# ISL6236A_DEMO.net
KiCad netlist of a schematic drawn in Altium Designer
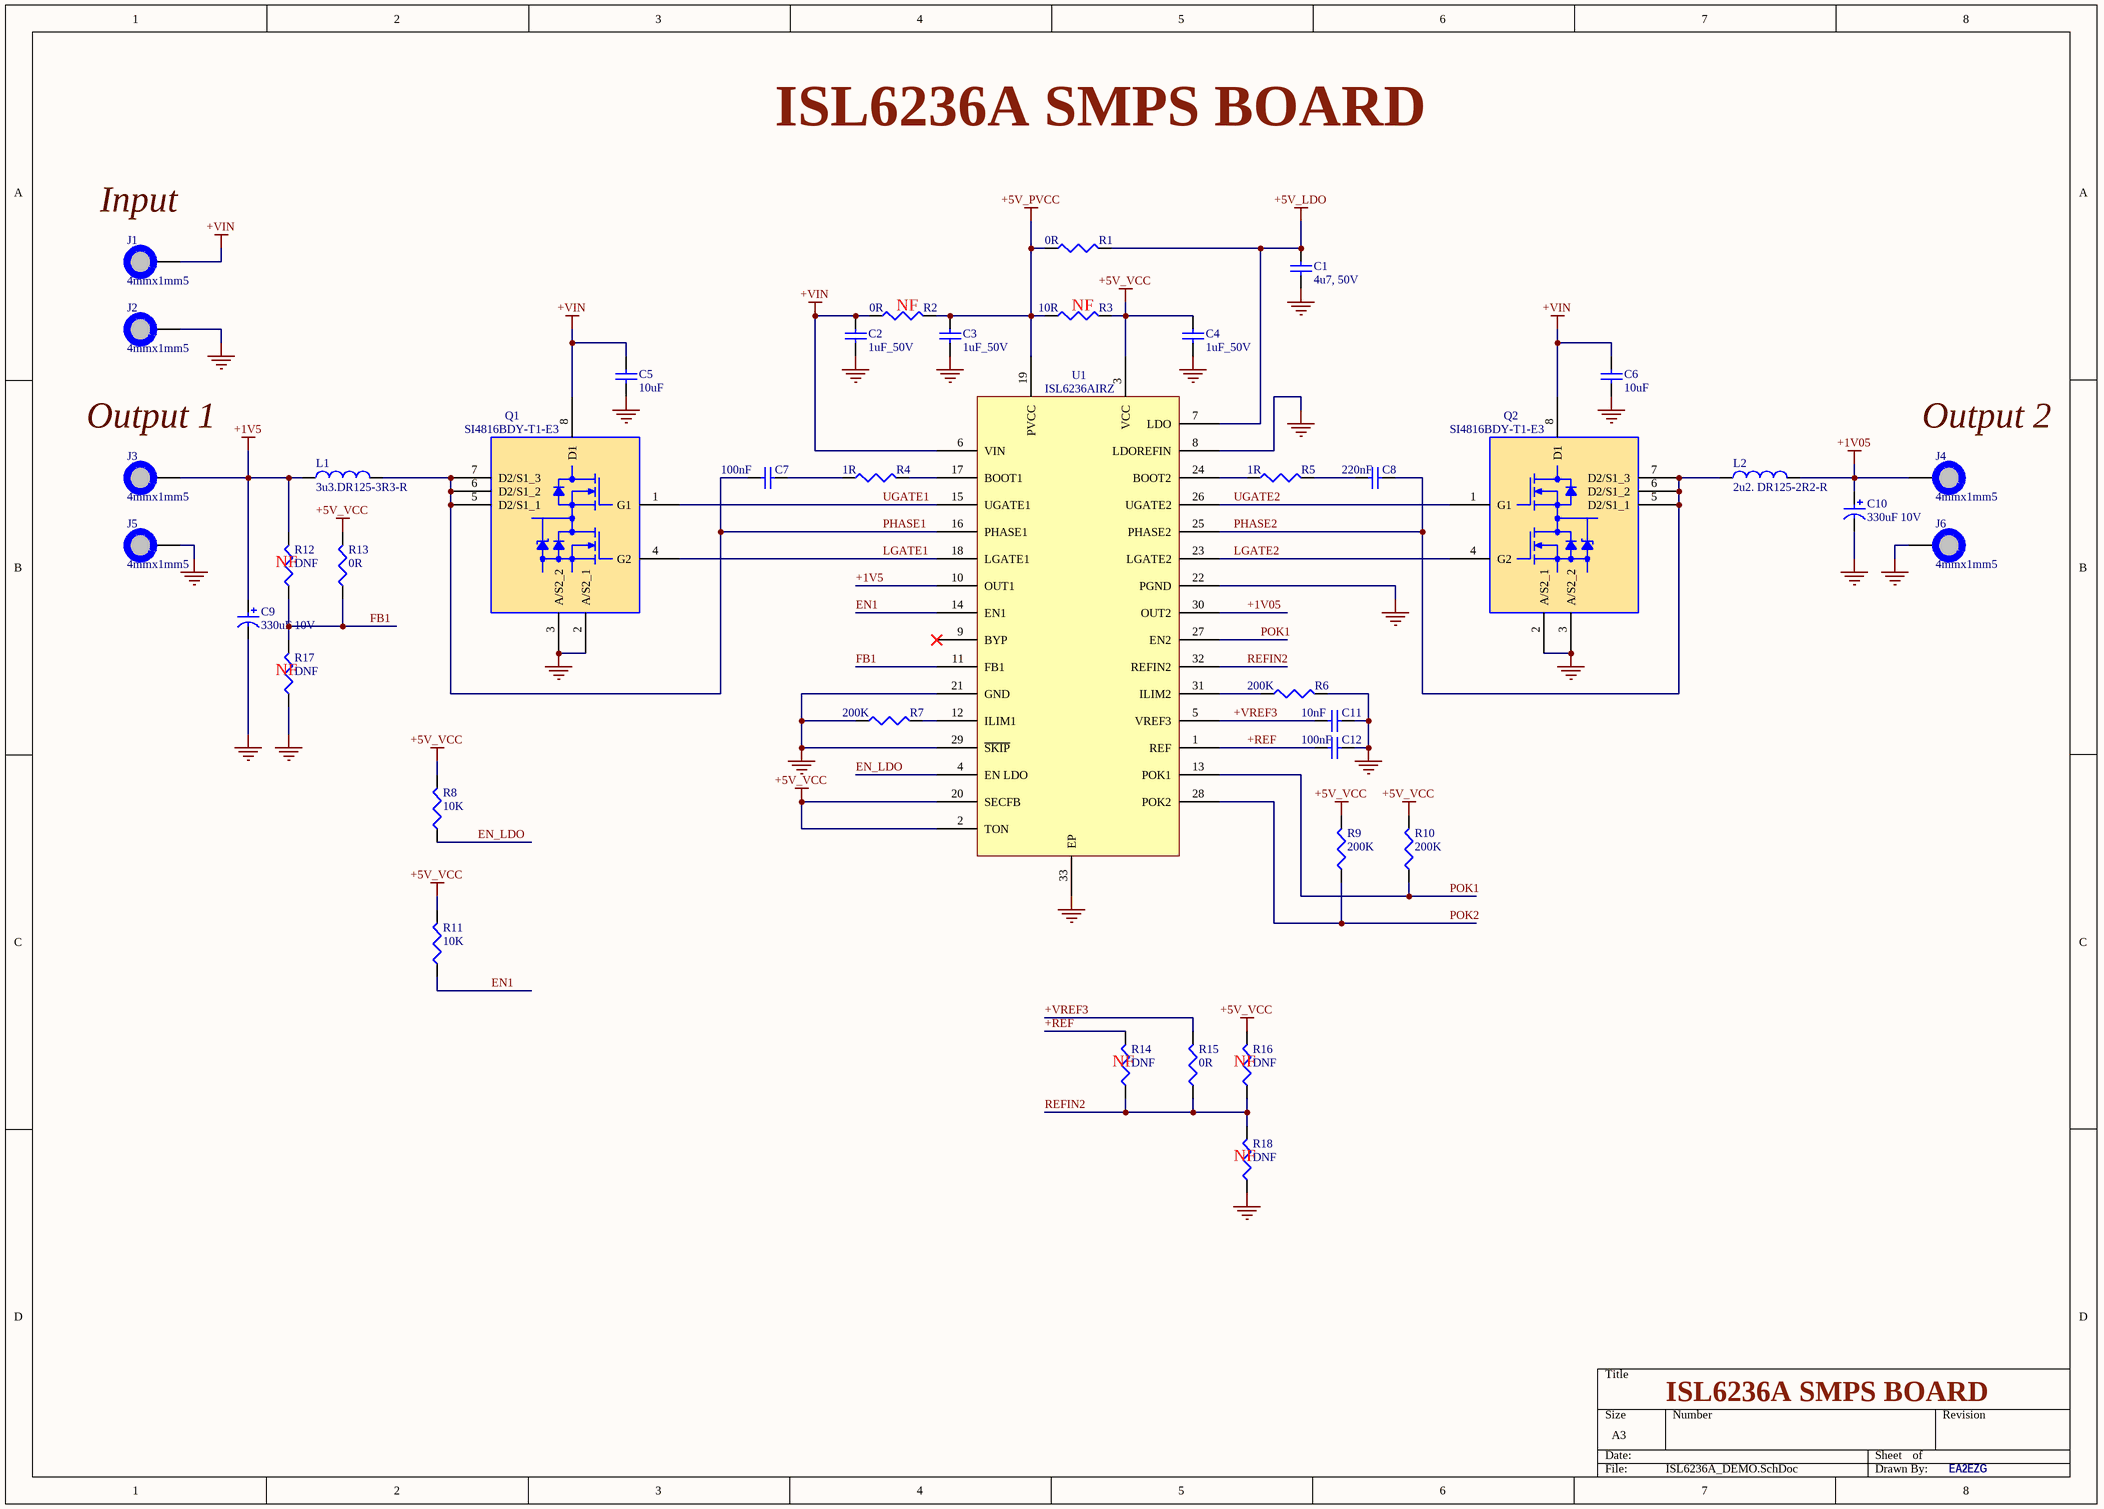
[diagram p0: ISL6236A_DEMO.SchDoc]

(export (version "E")
  (design (tool "Eeschema 10.0.6"))
  (components
    (comp (ref "C1")
      (value "4u7, 50V")
      (footprint "C1206")
      (description "C Series 1206 4.7 uF 50 V ±10 % Tolerance X5R SMT Multilayer Ceramic Capacitor")
      (fields
        (field (name "MANUFACTURER") "TDK")
        (field (name "MANUFACTURER PART NUMBER") "C3216X5R1H475K160AB")
      )
      (libsource (lib "ISL6236A_DEMO") (part "C3216X5R1H475K160AB"))
    )
    (comp (ref "C2")
      (value "1uF_50V")
      (footprint "C0805")
      (description "C Series 0805 1 uF 50 V ±10% Tolerance X7R SMT Multilayer Ceramic Capacitor")
      (fields
        (field (name "MANUFACTURER") "TDK")
        (field (name "MANUFACTURER PART NUMBER") "C2012X7R1H105K125AB")
      )
      (libsource (lib "ISL6236A_DEMO") (part "C2012X7R1H105K125AB"))
    )
    (comp (ref "C3")
      (value "1uF_50V")
      (footprint "C0805")
      (description "C Series 0805 1 uF 50 V ±10% Tolerance X7R SMT Multilayer Ceramic Capacitor")
      (fields
        (field (name "MANUFACTURER") "TDK")
        (field (name "MANUFACTURER PART NUMBER") "C2012X7R1H105K125AB")
      )
      (libsource (lib "ISL6236A_DEMO") (part "C2012X7R1H105K125AB"))
    )
    (comp (ref "C4")
      (value "1uF_50V")
      (footprint "C0805")
      (description "C Series 0805 1 uF 50 V ±10% Tolerance X7R SMT Multilayer Ceramic Capacitor")
      (fields
        (field (name "MANUFACTURER") "TDK")
        (field (name "MANUFACTURER PART NUMBER") "C2012X7R1H105K125AB")
      )
      (libsource (lib "ISL6236A_DEMO") (part "C2012X7R1H105K125AB"))
    )
    (comp (ref "C5")
      (value "10uF")
      (footprint "C1210")
      (description "Multilayer Ceramic Capacitor, 10 uF, 50 V, ± 10%, X5R, 1210 [3225 Metric]")
      (fields
        (field (name "MANUFACTURER") "KEMET")
        (field (name "MANUFACTURER PART NUMBER") "C1210C106K5PACTU")
      )
      (libsource (lib "ISL6236A_DEMO") (part "C1210C106K5PACTU"))
    )
    (comp (ref "C6")
      (value "10uF")
      (footprint "C1210")
      (description "Multilayer Ceramic Capacitor, 10 uF, 50 V, ± 10%, X5R, 1210 [3225 Metric]")
      (fields
        (field (name "MANUFACTURER") "KEMET")
        (field (name "MANUFACTURER PART NUMBER") "C1210C106K5PACTU")
      )
      (libsource (lib "ISL6236A_DEMO") (part "C1210C106K5PACTU"))
    )
    (comp (ref "C7")
      (value "100nF")
      (footprint "C0805")
      (description "Cap Cer 0805 0.1UF 50V X7R 10%")
      (fields
        (field (name "MANUFACTURER") "KEMET")
        (field (name "MANUFACTURER PART NUMBER") "C0805C104K5REC7210")
      )
      (libsource (lib "ISL6236A_DEMO") (part "C0805C104K5REC7210"))
    )
    (comp (ref "C8")
      (value "220nF")
      (footprint "C0805")
      (description "Cap Ceramic 0.22uF 50V X7R 10% SMD 2.0 x 1.2 mm OMD-CAP 125 C Plastic T/R")
      (fields
        (field (name "MANUFACTURER") "KEMET")
        (field (name "MANUFACTURER PART NUMBER") "C0805F224K5RACTU")
      )
      (libsource (lib "ISL6236A_DEMO") (part "C0805F224K5RACTU"))
    )
    (comp (ref "C9")
      (value "330uF 10V")
      (footprint "7343-43")
      (description "Cap Tant Solid 330uF 10V X CASE 20% (7.3 X 4.3 X 4mm) SMD 7343-43 0.004 Ohm 125 C T/R")
      (fields
        (field (name "MANUFACTURER") "KEMET")
        (field (name "MANUFACTURER PART NUMBER") "T530X337M010ATE004")
      )
      (libsource (lib "ISL6236A_DEMO") (part "T530X337M010ATE004"))
    )
    (comp (ref "C10")
      (value "330uF 10V")
      (footprint "7343-43")
      (description "Cap Tant Solid 330uF 10V X CASE 20% (7.3 X 4.3 X 4mm) SMD 7343-43 0.004 Ohm 125 C T/R")
      (fields
        (field (name "MANUFACTURER") "KEMET")
        (field (name "MANUFACTURER PART NUMBER") "T530X337M010ATE004")
      )
      (libsource (lib "ISL6236A_DEMO") (part "T530X337M010ATE004"))
    )
    (comp (ref "C11")
      (value "10nF")
      (footprint "C0805")
      (description "0805 C 10nF Ceramic Multilayer Capacitor; 50 VDC; +125degC; X7R Dielec; +/-10%")
      (fields
        (field (name "MANUFACTURER") "KEMET")
        (field (name "MANUFACTURER PART NUMBER") "C0805F103K5RACTU")
      )
      (libsource (lib "ISL6236A_DEMO") (part "C0805F103K5RACTU"))
    )
    (comp (ref "C12")
      (value "100nF")
      (footprint "C0805")
      (description "Cap Cer 0805 0.1UF 50V X7R 10%")
      (fields
        (field (name "MANUFACTURER") "KEMET")
        (field (name "MANUFACTURER PART NUMBER") "C0805C104K5REC7210")
      )
      (libsource (lib "ISL6236A_DEMO") (part "C0805C104K5REC7210"))
    )
    (comp (ref "J1")
      (value "4mmx1mm5")
      (footprint "PAD_WITH_HOLE_4mmx1mm5")
      (description "Pad with a hole 4mmx1mm5")
      (libsource (lib "ISL6236A_DEMO") (part "PAD_WITH_HOLE_4mmx1mm5"))
    )
    (comp (ref "J2")
      (value "4mmx1mm5")
      (footprint "PAD_WITH_HOLE_4mmx1mm5")
      (description "Pad with a hole 4mmx1mm5")
      (libsource (lib "ISL6236A_DEMO") (part "PAD_WITH_HOLE_4mmx1mm5"))
    )
    (comp (ref "J3")
      (value "4mmx1mm5")
      (footprint "PAD_WITH_HOLE_4mmx1mm5")
      (description "Pad with a hole 4mmx1mm5")
      (libsource (lib "ISL6236A_DEMO") (part "PAD_WITH_HOLE_4mmx1mm5"))
    )
    (comp (ref "J4")
      (value "4mmx1mm5")
      (footprint "PAD_WITH_HOLE_4mmx1mm5")
      (description "Pad with a hole 4mmx1mm5")
      (libsource (lib "ISL6236A_DEMO") (part "PAD_WITH_HOLE_4mmx1mm5"))
    )
    (comp (ref "J5")
      (value "4mmx1mm5")
      (footprint "PAD_WITH_HOLE_4mmx1mm5")
      (description "Pad with a hole 4mmx1mm5")
      (libsource (lib "ISL6236A_DEMO") (part "PAD_WITH_HOLE_4mmx1mm5"))
    )
    (comp (ref "J6")
      (value "4mmx1mm5")
      (footprint "PAD_WITH_HOLE_4mmx1mm5")
      (description "Pad with a hole 4mmx1mm5")
      (libsource (lib "ISL6236A_DEMO") (part "PAD_WITH_HOLE_4mmx1mm5"))
    )
    (comp (ref "L1")
      (value "3u3.DR125-3R3-R")
      (footprint "DR125")
      (description "Inductor Power Shielded Drum Core 3.3uH 20% 100KHz Ferrite 9.26A 6.3mOhm DCR T/R")
      (fields
        (field (name "MANUFACTURER") "Eaton Cooper")
        (field (name "MANUFACTURER PART NUMBER") "DR125-3R3-R")
      )
      (libsource (lib "ISL6236A_DEMO") (part "DR125-3R3-R"))
    )
    (comp (ref "L2")
      (value "2u2. DR125-2R2-R")
      (footprint "DR125")
      (description "Ind Power Shielded Wirewound 2.2uH 20% 100KHz Ferrite 10.9A T/R")
      (fields
        (field (name "MANUFACTURER") "Eaton Cooper")
        (field (name "MANUFACTURER PART NUMBER") "DR125-2R2-R")
      )
      (libsource (lib "ISL6236A_DEMO") (part "DR125-2R2-R"))
    )
    (comp (ref "Q1")
      (value "SI4816BDY-T1-E3")
      (footprint "SO-8")
      (description "Trans Mosfet N-ch 30V 5.8A/8.2A 8-PIN SOIC N T/r")
      (fields (field (name "MANUFACTURER") "Vishay Siliconix"))
      (libsource (lib "ISL6236A_DEMO") (part "SI4816BDY-T1-E3"))
    )
    (comp (ref "Q2")
      (value "SI4816BDY-T1-E3")
      (footprint "SO-8")
      (description "Trans Mosfet N-ch 30V 5.8A/8.2A 8-PIN SOIC N T/r")
      (fields (field (name "MANUFACTURER") "Vishay Siliconix"))
      (libsource (lib "ISL6236A_DEMO") (part "SI4816BDY-T1-E3"))
    )
    (comp (ref "R1")
      (value "0R")
      (footprint "R0805")
      (description "Res Thick Film 0805 0 Ohm Sulfur Resistant Pad SMD Automotive T/R")
      (fields
        (field (name "MANUFACTURER") "KOA Speer")
        (field (name "MANUFACTURER PART NUMBER") "RK73Z2ARTTD")
      )
      (libsource (lib "ISL6236A_DEMO") (part "RK73Z2ARTTD"))
    )
    (comp (ref "R2")
      (value "0R")
      (footprint "R0805")
      (description "Res Thick Film 0805 0 Ohm Sulfur Resistant Pad SMD Automotive T/R")
      (fields
        (field (name "MANUFACTURER") "KOA Speer")
        (field (name "MANUFACTURER PART NUMBER") "RK73Z2ARTTD")
      )
      (libsource (lib "ISL6236A_DEMO") (part "RK73Z2ARTTD"))
    )
    (comp (ref "R3")
      (value "10R")
      (footprint "R0805")
      (description "Res Thick Film 0805 10 Ohm 1% 0.125W(1/8W) ±200ppm/C Pad SMD Automotive T/R")
      (fields
        (field (name "MANUFACTURER") "Yageo")
        (field (name "MANUFACTURER PART NUMBER") "AC0805FR-0710RL")
      )
      (libsource (lib "ISL6236A_DEMO") (part "AC0805FR-0710RL"))
    )
    (comp (ref "R4")
      (value "1R")
      (footprint "R0805")
      (description "Res Thick Film 0805 1 Ohm 1% 0.125W(1/8W) ±200ppm/C Pad SMD Automotive T/R")
      (fields
        (field (name "MANUFACTURER") "Yageo")
        (field (name "MANUFACTURER PART NUMBER") "AC0805FR-071RL")
      )
      (libsource (lib "ISL6236A_DEMO") (part "AC0805FR-071RL"))
    )
    (comp (ref "R5")
      (value "1R")
      (footprint "R0805")
      (description "Res Thick Film 0805 1 Ohm 1% 0.125W(1/8W) ±200ppm/C Pad SMD Automotive T/R")
      (fields
        (field (name "MANUFACTURER") "Yageo")
        (field (name "MANUFACTURER PART NUMBER") "AC0805FR-071RL")
      )
      (libsource (lib "ISL6236A_DEMO") (part "AC0805FR-071RL"))
    )
    (comp (ref "R6")
      (value "200K")
      (footprint "R0805")
      (description "Res Thick Film 0805 200K Ohm 1% 0.125W(1/8W) ±100ppm/C Pad SMD Automotive T/R")
      (fields
        (field (name "MANUFACTURER") "Yageo")
        (field (name "MANUFACTURER PART NUMBER") "AC0805FR-07200KL")
      )
      (libsource (lib "ISL6236A_DEMO") (part "AC0805FR-07200KL"))
    )
    (comp (ref "R7")
      (value "200K")
      (footprint "R0805")
      (description "Res Thick Film 0805 200K Ohm 1% 0.125W(1/8W) ±100ppm/C Pad SMD Automotive T/R")
      (fields
        (field (name "MANUFACTURER") "Yageo")
        (field (name "MANUFACTURER PART NUMBER") "AC0805FR-07200KL")
      )
      (libsource (lib "ISL6236A_DEMO") (part "AC0805FR-07200KL"))
    )
    (comp (ref "R8")
      (value "10K")
      (footprint "R0805")
      (description "Res, 10K, 1%, 0.125W, Thin Film, 0805 Rohs Compliant: Yes ¦Yageo RP0805FRE0710KL")
      (fields
        (field (name "MANUFACTURER") "Yageo")
        (field (name "MANUFACTURER PART NUMBER") "RP0805FRE0710KL")
      )
      (libsource (lib "ISL6236A_DEMO") (part "RP0805FRE0710KL"))
    )
    (comp (ref "R9")
      (value "200K")
      (footprint "R0805")
      (description "Res Thick Film 0805 200K Ohm 1% 0.125W(1/8W) ±100ppm/C Pad SMD Automotive T/R")
      (fields
        (field (name "MANUFACTURER") "Yageo")
        (field (name "MANUFACTURER PART NUMBER") "AC0805FR-07200KL")
      )
      (libsource (lib "ISL6236A_DEMO") (part "AC0805FR-07200KL"))
    )
    (comp (ref "R10")
      (value "200K")
      (footprint "R0805")
      (description "Res Thick Film 0805 200K Ohm 1% 0.125W(1/8W) ±100ppm/C Pad SMD Automotive T/R")
      (fields
        (field (name "MANUFACTURER") "Yageo")
        (field (name "MANUFACTURER PART NUMBER") "AC0805FR-07200KL")
      )
      (libsource (lib "ISL6236A_DEMO") (part "AC0805FR-07200KL"))
    )
    (comp (ref "R11")
      (value "10K")
      (footprint "R0805")
      (description "Res, 10K, 1%, 0.125W, Thin Film, 0805 Rohs Compliant: Yes ¦Yageo RP0805FRE0710KL")
      (fields
        (field (name "MANUFACTURER") "Yageo")
        (field (name "MANUFACTURER PART NUMBER") "RP0805FRE0710KL")
      )
      (libsource (lib "ISL6236A_DEMO") (part "RP0805FRE0710KL"))
    )
    (comp (ref "R12") (value "DNF") (footprint "R0805") (libsource (lib "ISL6236A_DEMO") (part "RES")))
    (comp (ref "R13")
      (value "0R")
      (footprint "R0805")
      (description "Res Thick Film 0805 0 Ohm Sulfur Resistant Pad SMD Automotive T/R")
      (fields
        (field (name "MANUFACTURER") "KOA Speer")
        (field (name "MANUFACTURER PART NUMBER") "RK73Z2ARTTD")
      )
      (libsource (lib "ISL6236A_DEMO") (part "RK73Z2ARTTD"))
    )
    (comp (ref "R14") (value "DNF") (footprint "R0805") (libsource (lib "ISL6236A_DEMO") (part "RES")))
    (comp (ref "R15")
      (value "0R")
      (footprint "R0805")
      (description "Res Thick Film 0805 0 Ohm Sulfur Resistant Pad SMD Automotive T/R")
      (fields
        (field (name "MANUFACTURER") "KOA Speer")
        (field (name "MANUFACTURER PART NUMBER") "RK73Z2ARTTD")
      )
      (libsource (lib "ISL6236A_DEMO") (part "RK73Z2ARTTD"))
    )
    (comp (ref "R16") (value "DNF") (footprint "R0805") (libsource (lib "ISL6236A_DEMO") (part "RES")))
    (comp (ref "R17") (value "DNF") (footprint "R0805") (libsource (lib "ISL6236A_DEMO") (part "RES")))
    (comp (ref "R18") (value "DNF") (footprint "R0805") (libsource (lib "ISL6236A_DEMO") (part "RES")))
    (comp (ref "U1")
      (value "ISL6236AIRZ")
      (footprint "L32.5X5B")
      (description "Soft Sw PWM Cntrlr 2-OUT Power Supply Controller 200KHz/300KHz/400KHz/500KHz 32-Pin QFN EP")
      (fields (field (name "MANUFACTURER") "Renesas"))
      (libsource (lib "ISL6236A_DEMO") (part "ISL6236AIRZ"))
    )
  )
  (nets
    (net (code "1") (name "+1V5") (class "Default")
      (node (ref "C9") (pin "1") (pinfunction "1_1") (pintype "passive"))
      (node (ref "J3") (pin "1") (pinfunction "1_1") (pintype "passive"))
      (node (ref "L1") (pin "1") (pinfunction "1_1") (pintype "passive"))
      (node (ref "R12") (pin "2") (pinfunction "2_2") (pintype "passive"))
      (node (ref "U1") (pin "10") (pinfunction "OUT1_10") (pintype "passive"))
    )
    (net (code "2") (name "+1V05") (class "Default")
      (node (ref "C10") (pin "1") (pinfunction "1_1") (pintype "passive"))
      (node (ref "J4") (pin "1") (pinfunction "1_1") (pintype "passive"))
      (node (ref "L2") (pin "2") (pinfunction "2_2") (pintype "passive"))
      (node (ref "U1") (pin "30") (pinfunction "OUT2_30") (pintype "passive"))
    )
    (net (code "3") (name "+5V_LDO") (class "Default")
      (node (ref "C1") (pin "2") (pinfunction "2_2") (pintype "passive"))
      (node (ref "R1") (pin "2") (pinfunction "2_2") (pintype "passive"))
      (node (ref "U1") (pin "7") (pinfunction "LDO_7") (pintype "passive"))
    )
    (net (code "4") (name "+5V_PVCC") (class "Default")
      (node (ref "C3") (pin "2") (pinfunction "2_2") (pintype "passive"))
      (node (ref "R1") (pin "1") (pinfunction "1_1") (pintype "passive"))
      (node (ref "R2") (pin "2") (pinfunction "2_2") (pintype "passive"))
      (node (ref "R3") (pin "1") (pinfunction "1_1") (pintype "passive"))
      (node (ref "U1") (pin "19") (pinfunction "PVCC_19") (pintype "passive"))
    )
    (net (code "5") (name "+5V_VCC") (class "Default")
      (node (ref "C4") (pin "2") (pinfunction "2_2") (pintype "passive"))
      (node (ref "R10") (pin "2") (pinfunction "2_2") (pintype "passive"))
      (node (ref "R11") (pin "2") (pinfunction "2_2") (pintype "passive"))
      (node (ref "R13") (pin "2") (pinfunction "2_2") (pintype "passive"))
      (node (ref "R16") (pin "2") (pinfunction "2_2") (pintype "passive"))
      (node (ref "R3") (pin "2") (pinfunction "2_2") (pintype "passive"))
      (node (ref "R8") (pin "2") (pinfunction "2_2") (pintype "passive"))
      (node (ref "R9") (pin "2") (pinfunction "2_2") (pintype "passive"))
      (node (ref "U1") (pin "2") (pinfunction "TON_2") (pintype "passive"))
      (node (ref "U1") (pin "20") (pinfunction "SECFB_20") (pintype "passive"))
      (node (ref "U1") (pin "3") (pinfunction "VCC_3") (pintype "passive"))
    )
    (net (code "6") (name "+VIN") (class "Default")
      (node (ref "C2") (pin "2") (pinfunction "2_2") (pintype "passive"))
      (node (ref "C5") (pin "2") (pinfunction "2_2") (pintype "passive"))
      (node (ref "C6") (pin "2") (pinfunction "2_2") (pintype "passive"))
      (node (ref "J1") (pin "1") (pinfunction "1_1") (pintype "passive"))
      (node (ref "Q1") (pin "8") (pinfunction "D1_8") (pintype "passive"))
      (node (ref "Q2") (pin "8") (pinfunction "D1_8") (pintype "passive"))
      (node (ref "R2") (pin "1") (pinfunction "1_1") (pintype "passive"))
      (node (ref "U1") (pin "6") (pinfunction "VIN_6") (pintype "passive"))
    )
    (net (code "7") (name "/+REF") (class "Default")
      (node (ref "C12") (pin "1") (pinfunction "1_1") (pintype "passive"))
      (node (ref "R14") (pin "2") (pinfunction "2_2") (pintype "passive"))
      (node (ref "U1") (pin "1") (pinfunction "REF_1") (pintype "passive"))
    )
    (net (code "8") (name "/+VREF3") (class "Default")
      (node (ref "C11") (pin "2") (pinfunction "2_2") (pintype "passive"))
      (node (ref "R15") (pin "2") (pinfunction "2_2") (pintype "passive"))
      (node (ref "U1") (pin "5") (pinfunction "VREF3_5") (pintype "passive"))
    )
    (net (code "9") (name "/EN1") (class "Default")
      (node (ref "R11") (pin "1") (pinfunction "1_1") (pintype "passive"))
      (node (ref "U1") (pin "14") (pinfunction "EN1_14") (pintype "passive"))
    )
    (net (code "10") (name "/EN_LDO") (class "Default")
      (node (ref "R8") (pin "1") (pinfunction "1_1") (pintype "passive"))
      (node (ref "U1") (pin "4") (pinfunction "EN_LDO_4") (pintype "passive"))
    )
    (net (code "11") (name "/FB1") (class "Default")
      (node (ref "R12") (pin "1") (pinfunction "1_1") (pintype "passive"))
      (node (ref "R13") (pin "1") (pinfunction "1_1") (pintype "passive"))
      (node (ref "R17") (pin "2") (pinfunction "2_2") (pintype "passive"))
      (node (ref "U1") (pin "11") (pinfunction "FB1_11") (pintype "passive"))
    )
    (net (code "12") (name "/LGATE1") (class "Default")
      (node (ref "Q1") (pin "4") (pinfunction "G2_4") (pintype "passive"))
      (node (ref "U1") (pin "18") (pinfunction "LGATE1_18") (pintype "passive"))
    )
    (net (code "13") (name "/LGATE2") (class "Default")
      (node (ref "Q2") (pin "4") (pinfunction "G2_4") (pintype "passive"))
      (node (ref "U1") (pin "23") (pinfunction "LGATE2_23") (pintype "passive"))
    )
    (net (code "14") (name "/PHASE1") (class "Default")
      (node (ref "C7") (pin "1") (pinfunction "1_1") (pintype "passive"))
      (node (ref "L1") (pin "2") (pinfunction "2_2") (pintype "passive"))
      (node (ref "Q1") (pin "5") (pinfunction "D2/S1_1_5") (pintype "passive"))
      (node (ref "Q1") (pin "6") (pinfunction "D2/S1_2_6") (pintype "passive"))
      (node (ref "Q1") (pin "7") (pinfunction "D2/S1_3_7") (pintype "passive"))
      (node (ref "U1") (pin "16") (pinfunction "PHASE1_16") (pintype "passive"))
    )
    (net (code "15") (name "/PHASE2") (class "Default")
      (node (ref "C8") (pin "2") (pinfunction "2_2") (pintype "passive"))
      (node (ref "L2") (pin "1") (pinfunction "1_1") (pintype "passive"))
      (node (ref "Q2") (pin "5") (pinfunction "D2/S1_1_5") (pintype "passive"))
      (node (ref "Q2") (pin "6") (pinfunction "D2/S1_2_6") (pintype "passive"))
      (node (ref "Q2") (pin "7") (pinfunction "D2/S1_3_7") (pintype "passive"))
      (node (ref "U1") (pin "25") (pinfunction "PHASE2_25") (pintype "passive"))
    )
    (net (code "16") (name "/POK1") (class "Default")
      (node (ref "R10") (pin "1") (pinfunction "1_1") (pintype "passive"))
      (node (ref "U1") (pin "13") (pinfunction "POK1_13") (pintype "passive"))
      (node (ref "U1") (pin "27") (pinfunction "EN2_27") (pintype "passive"))
    )
    (net (code "17") (name "/POK2") (class "Default")
      (node (ref "R9") (pin "1") (pinfunction "1_1") (pintype "passive"))
      (node (ref "U1") (pin "28") (pinfunction "POK2_28") (pintype "passive"))
    )
    (net (code "18") (name "/REFIN2") (class "Default")
      (node (ref "R14") (pin "1") (pinfunction "1_1") (pintype "passive"))
      (node (ref "R15") (pin "1") (pinfunction "1_1") (pintype "passive"))
      (node (ref "R16") (pin "1") (pinfunction "1_1") (pintype "passive"))
      (node (ref "R18") (pin "2") (pinfunction "2_2") (pintype "passive"))
      (node (ref "U1") (pin "32") (pinfunction "REFIN2_32") (pintype "passive"))
    )
    (net (code "19") (name "/UGATE1") (class "Default")
      (node (ref "Q1") (pin "1") (pinfunction "G1_1") (pintype "passive"))
      (node (ref "U1") (pin "15") (pinfunction "UGATE1_15") (pintype "passive"))
    )
    (net (code "20") (name "/UGATE2") (class "Default")
      (node (ref "Q2") (pin "1") (pinfunction "G1_1") (pintype "passive"))
      (node (ref "U1") (pin "26") (pinfunction "UGATE2_26") (pintype "passive"))
    )
    (net (code "21") (name "GND") (class "Default")
      (node (ref "C1") (pin "1") (pinfunction "1_1") (pintype "passive"))
      (node (ref "C10") (pin "2") (pinfunction "2_2") (pintype "passive"))
      (node (ref "C11") (pin "1") (pinfunction "1_1") (pintype "passive"))
      (node (ref "C12") (pin "2") (pinfunction "2_2") (pintype "passive"))
      (node (ref "C2") (pin "1") (pinfunction "1_1") (pintype "passive"))
      (node (ref "C3") (pin "1") (pinfunction "1_1") (pintype "passive"))
      (node (ref "C4") (pin "1") (pinfunction "1_1") (pintype "passive"))
      (node (ref "C5") (pin "1") (pinfunction "1_1") (pintype "passive"))
      (node (ref "C6") (pin "1") (pinfunction "1_1") (pintype "passive"))
      (node (ref "C9") (pin "2") (pinfunction "2_2") (pintype "passive"))
      (node (ref "J2") (pin "1") (pinfunction "1_1") (pintype "passive"))
      (node (ref "J5") (pin "1") (pinfunction "1_1") (pintype "passive"))
      (node (ref "J6") (pin "1") (pinfunction "1_1") (pintype "passive"))
      (node (ref "Q1") (pin "2") (pinfunction "A/S2_1_2") (pintype "passive"))
      (node (ref "Q1") (pin "3") (pinfunction "A/S2_2_3") (pintype "passive"))
      (node (ref "Q2") (pin "2") (pinfunction "A/S2_1_2") (pintype "passive"))
      (node (ref "Q2") (pin "3") (pinfunction "A/S2_2_3") (pintype "passive"))
      (node (ref "R17") (pin "1") (pinfunction "1_1") (pintype "passive"))
      (node (ref "R18") (pin "1") (pinfunction "1_1") (pintype "passive"))
      (node (ref "R6") (pin "2") (pinfunction "2_2") (pintype "passive"))
      (node (ref "R7") (pin "1") (pinfunction "1_1") (pintype "passive"))
      (node (ref "U1") (pin "21") (pinfunction "GND_21") (pintype "passive"))
      (node (ref "U1") (pin "22") (pinfunction "PGND_22") (pintype "passive"))
      (node (ref "U1") (pin "29") (pinfunction "~{SKIP}_29") (pintype "passive"))
      (node (ref "U1") (pin "33") (pinfunction "EP_33") (pintype "passive"))
      (node (ref "U1") (pin "8") (pinfunction "LDOREFIN_8") (pintype "passive"))
    )
    (net (code "22") (name "Net-(C7-Pad2)") (class "Default")
      (node (ref "C7") (pin "2") (pinfunction "2_2") (pintype "passive"))
      (node (ref "R4") (pin "1") (pinfunction "1_1") (pintype "passive"))
    )
    (net (code "23") (name "Net-(C8-Pad1)") (class "Default")
      (node (ref "C8") (pin "1") (pinfunction "1_1") (pintype "passive"))
      (node (ref "R5") (pin "2") (pinfunction "2_2") (pintype "passive"))
    )
    (net (code "24") (name "Net-(U1-BOOT1)") (class "Default")
      (node (ref "R4") (pin "2") (pinfunction "2_2") (pintype "passive"))
      (node (ref "U1") (pin "17") (pinfunction "BOOT1_17") (pintype "passive"))
    )
    (net (code "25") (name "Net-(U1-BOOT2)") (class "Default")
      (node (ref "R5") (pin "1") (pinfunction "1_1") (pintype "passive"))
      (node (ref "U1") (pin "24") (pinfunction "BOOT2_24") (pintype "passive"))
    )
    (net (code "26") (name "Net-(U1-ILIM1)") (class "Default")
      (node (ref "R7") (pin "2") (pinfunction "2_2") (pintype "passive"))
      (node (ref "U1") (pin "12") (pinfunction "ILIM1_12") (pintype "passive"))
    )
    (net (code "27") (name "Net-(U1-ILIM2)") (class "Default")
      (node (ref "R6") (pin "1") (pinfunction "1_1") (pintype "passive"))
      (node (ref "U1") (pin "31") (pinfunction "ILIM2_31") (pintype "passive"))
    )
    (net (code "28") (name "unconnected-(U1-BYP-Pad9)") (class "Default")
      (node (ref "U1") (pin "9") (pinfunction "BYP_9") (pintype "passive+no_connect"))
    )
  )
)
